# Peggy_Receiver.net
KiCad netlist of a schematic drawn in Altium Designer
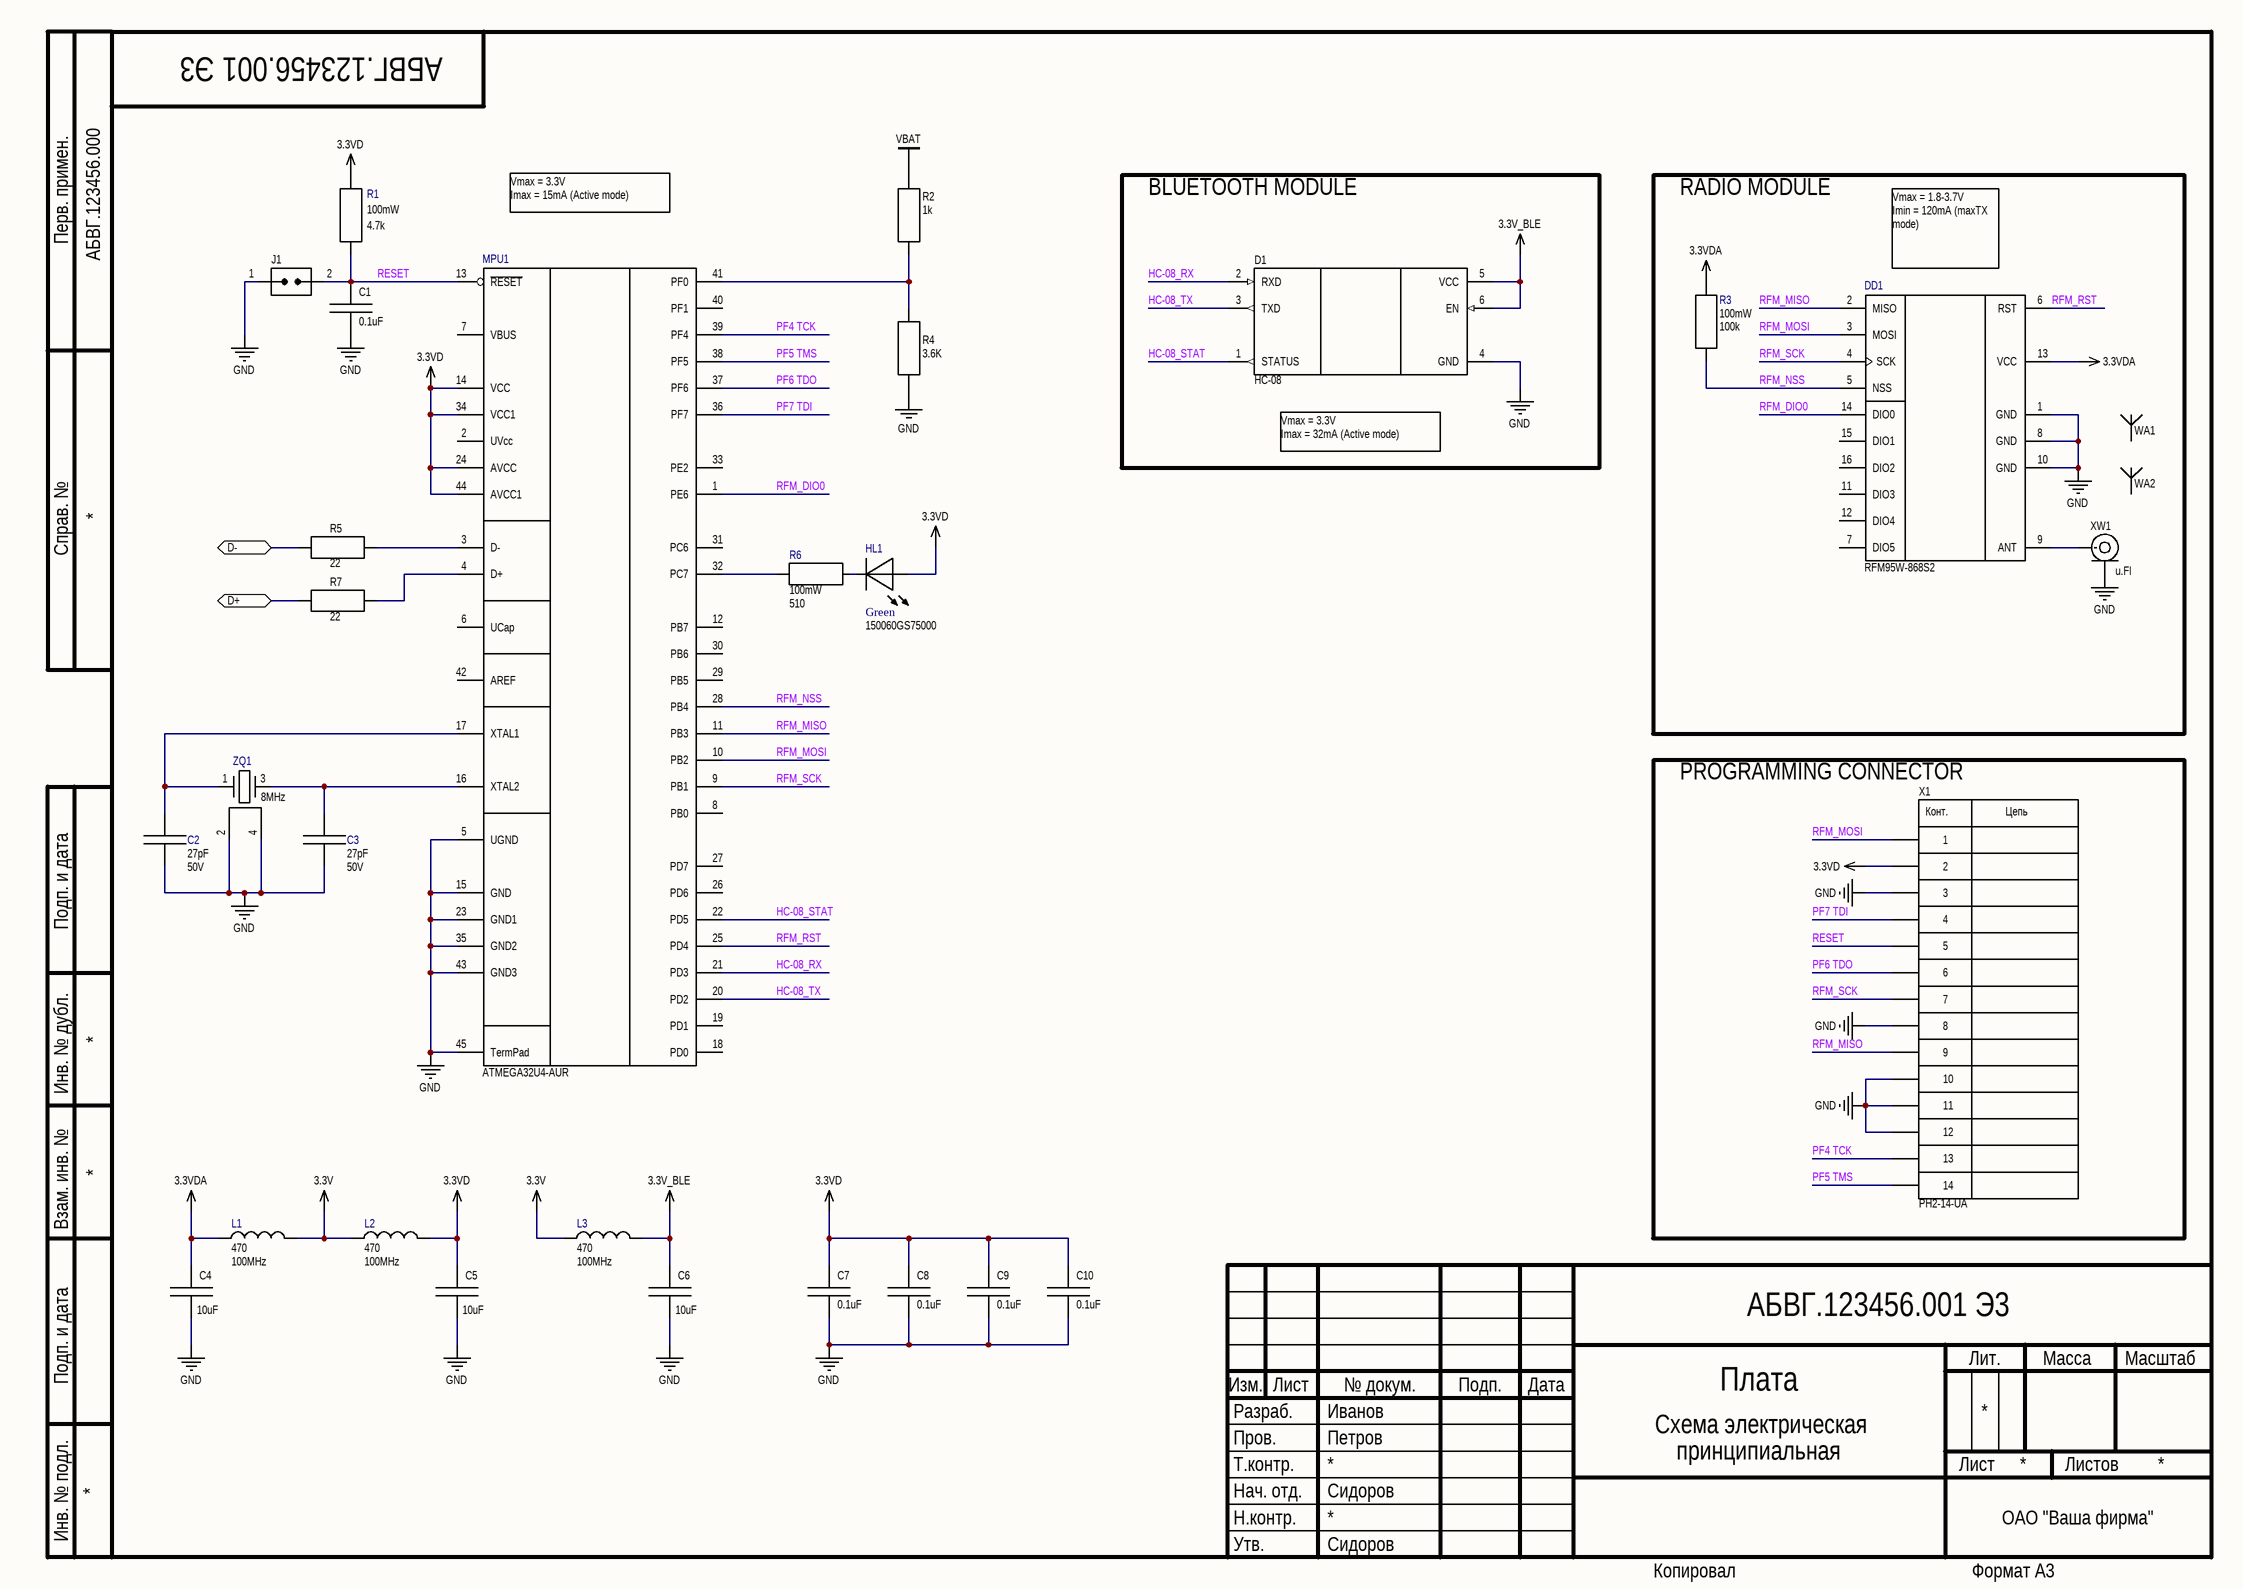
[diagram p0: Блок МК и радиомодуля Peggy Receiver.SchDoc]

(export (version "E")
  (design (tool "Eeschema 10.0.6"))
  (components
    (comp (ref "C1")
      (value "0.1uF")
      (footprint "CH0603C")
      (fields (field (name "MANUFACTURER") "Murata Electronics"))
      (libsource (lib "Discrete") (part "Capacitor"))
    )
    (comp (ref "C2")
      (value "CC0603JPNPO9BN270")
      (footprint "CAPC1608X87X35NL15T15")
      (description "0603 50V C0G 27pF 5% multilayer ceramic capacitor")
      (fields
        (field (name "MANUFACTURER") "YAGEO")
        (field (name "CAPACITANCE") "27pF")
        (field (name "VOLTAGE RATING") "50V")
        (field (name "TOLERANCE") "5%")
      )
      (libsource (lib "Sergek Concord Server") (part "CAP-NP-2"))
    )
    (comp (ref "C3")
      (value "CC0603JPNPO9BN270")
      (footprint "CAPC1608X87X35NL15T15")
      (description "0603 50V C0G 27pF 5% multilayer ceramic capacitor")
      (fields
        (field (name "MANUFACTURER") "YAGEO")
        (field (name "CAPACITANCE") "27pF")
        (field (name "VOLTAGE RATING") "50V")
        (field (name "TOLERANCE") "5%")
      )
      (libsource (lib "Sergek Concord Server") (part "CAP-NP-2"))
    )
    (comp (ref "C4")
      (value "10uF")
      (footprint "standard_dis:CH1206C")
      (description "CAP CER 10UF 16V X7R 1206")
      (fields (field (name "MANUFACTURER") "Murata Electronics"))
      (libsource (lib "Discrete") (part "Capacitor"))
    )
    (comp (ref "C5")
      (value "10uF")
      (footprint "standard_dis:CH1206C")
      (description "CAP CER 10UF 16V X7R 1206")
      (fields (field (name "MANUFACTURER") "Murata Electronics"))
      (libsource (lib "Discrete") (part "Capacitor"))
    )
    (comp (ref "C6")
      (value "10uF")
      (footprint "standard_dis:CH1206C")
      (description "CAP CER 10UF 16V X7R 1206")
      (fields (field (name "MANUFACTURER") "Murata Electronics"))
      (libsource (lib "Discrete") (part "Capacitor"))
    )
    (comp (ref "C7")
      (value "0.1uF")
      (footprint "CH0603C")
      (fields (field (name "MANUFACTURER") "Murata Electronics"))
      (libsource (lib "Discrete") (part "Capacitor"))
    )
    (comp (ref "C8")
      (value "0.1uF")
      (footprint "CH0603C")
      (fields (field (name "MANUFACTURER") "Murata Electronics"))
      (libsource (lib "Discrete") (part "Capacitor"))
    )
    (comp (ref "C9")
      (value "0.1uF")
      (footprint "CH0603C")
      (fields (field (name "MANUFACTURER") "Murata Electronics"))
      (libsource (lib "Discrete") (part "Capacitor"))
    )
    (comp (ref "C10")
      (value "0.1uF")
      (footprint "CH0603C")
      (fields (field (name "MANUFACTURER") "Murata Electronics"))
      (libsource (lib "Discrete") (part "Capacitor"))
    )
    (comp (ref "D1")
      (value "HC-08")
      (footprint "custom_mod:MOD: SH-HC-08")
      (description "Bluetooth 4.0 module")
      (fields (field (name "MANUFACTURER") "China"))
      (libsource (lib "Module") (part "HC-08"))
    )
    (comp (ref "DD1")
      (value "RFM95W-868S2")
      (footprint "RFM95W-868S2")
      (description "RF TXRX MODULE ISM<1GHZ")
      (fields
        (field (name "MANUFACTURER") "RF Solutions")
        (field (name "MANUFACTURER PART NUMBER") "RFM95W-868S2")
      )
      (libsource (lib "Sergek Concord Server") (part "HPD13A (RFM95)"))
    )
    (comp (ref "HL1")
      (value "150060GS75000")
      (footprint "CH0603LG")
      (description "WURTH ELEKTRONIK - 150060GS75000 - LED, Green, 520 nm, 3.2 V, 30 mA, 430 mcd RoHS Compliant: Yes")
      (fields
        (field (name "COLOR") "Green")
        (field (name "MANUFACTURER PART NUMBER") "150060GS75000")
        (field (name "MANUFACTURER") "Würth Elektronik")
      )
      (libsource (lib "Sergek Concord Server") (part "Symbol"))
    )
    (comp (ref "J1")
      (value "Jumper-2")
      (footprint "custom_con:CON: JUMPER_2")
      (description "Jumper")
      (fields (field (name "MANUFACTURER") "China"))
      (libsource (lib "Connectors") (part "Jumper-2"))
    )
    (comp (ref "L1")
      (value "MH2029-471Y")
      (footprint "MH2029-471Y-Footprint-1")
      (description "Ferrite Beads High Current Chip 470Ohm 25% 100MHz 1A 0.2Ohm DCR 0805 T/R")
      (fields
        (field (name "TOLERANCE") "25%")
        (field (name "IMPEDANCE") "470")
        (field (name "TEST FREQUENCY") "100MHz")
        (field (name "MANUFACTURER") "Bourns Inc.")
      )
      (libsource (lib "Sergek Concord Server") (part "IND-2"))
    )
    (comp (ref "L2")
      (value "MH2029-471Y")
      (footprint "MH2029-471Y-Footprint-1")
      (description "Ferrite Beads High Current Chip 470Ohm 25% 100MHz 1A 0.2Ohm DCR 0805 T/R")
      (fields
        (field (name "TOLERANCE") "25%")
        (field (name "IMPEDANCE") "470")
        (field (name "TEST FREQUENCY") "100MHz")
        (field (name "MANUFACTURER") "Bourns Inc.")
      )
      (libsource (lib "Sergek Concord Server") (part "IND-2"))
    )
    (comp (ref "L3")
      (value "MH2029-471Y")
      (footprint "MH2029-471Y-Footprint-1")
      (description "Ferrite Beads High Current Chip 470Ohm 25% 100MHz 1A 0.2Ohm DCR 0805 T/R")
      (fields
        (field (name "TOLERANCE") "25%")
        (field (name "IMPEDANCE") "470")
        (field (name "TEST FREQUENCY") "100MHz")
        (field (name "MANUFACTURER") "Bourns Inc.")
      )
      (libsource (lib "Sergek Concord Server") (part "IND-2"))
    )
    (comp (ref "MPU1")
      (value "ATMEGA32U4-AU")
      (footprint "ATMEGA32U4-MU")
      (fields
        (field (name "MANUFACTURER PART NUMBER") "ATMEGA32U4-AUR")
        (field (name "MANUFACTURER") "Atmel")
      )
      (libsource (lib "Sergek Concord Server") (part "ATMEGA32U4-AU"))
    )
    (comp (ref "R1")
      (value "RMCF0603FT4K70")
      (footprint "CH0603R")
      (description "Res Thick Film 0603 4.7K Ohm 1% 1/10W 100ppm/C Molded SMD SMD Paper T/R")
      (fields
        (field (name "TOLERANCE") "1%")
        (field (name "POWER RATING") "100mW")
        (field (name "RESISTANCE") "4.7k")
        (field (name "MANUFACTURER") "Stackpole Electronics Inc")
      )
      (libsource (lib "Sergek Concord Server") (part "RES-2"))
    )
    (comp (ref "R2")
      (value "1k")
      (footprint "standard_dis:CH0603R")
      (fields (field (name "MANUFACTURER") "YAGEO"))
      (libsource (lib "Discrete") (part "Resistor"))
    )
    (comp (ref "R3")
      (value "100k")
      (footprint "RESC1608X55X25NL10T15")
      (description "Chip Resistor, 100 KOhm, +/- 1%, 0.1 W, -55 to 155 degC, 0603 (1608 Metric)")
      (fields
        (field (name "POWER") "100mW")
        (field (name "TOLERANCE") "1%")
        (field (name "Comment") "Resistor 100k +/-1% 0603 100 mW")
      )
      (libsource (lib "Sergek Concord Server") (part "RES-2"))
    )
    (comp (ref "R4")
      (value "3.6K")
      (footprint "standard_dis:CH0603R")
      (description "RES 3.6K OHM 1% 1/10W 0603")
      (fields (field (name "MANUFACTURER") "YAGEO"))
      (libsource (lib "Discrete") (part "Resistor"))
    )
    (comp (ref "R5")
      (value "22")
      (footprint "standard_dis:CH0603R")
      (description "RES 22 OHM 1% 1/10W 0603")
      (fields (field (name "MANUFACTURER") "YAGEO"))
      (libsource (lib "") (part "Resistor_1"))
    )
    (comp (ref "R6")
      (value "RMCF0603JT510R")
      (footprint "RESC1608X55X25NL10T15")
      (description "510 Ohms ±5% 0.1W, 1/10W Chip Resistor 0603 (1608 Metric) Automotive AEC-Q200 Thick Film")
      (fields
        (field (name "MANUFACTURER") "Stackpole Electronics Inc")
        (field (name "POWER RATING") "100mW")
        (field (name "RESISTANCE") "510")
        (field (name "TOLERANCE") "5%")
      )
      (libsource (lib "") (part "RES-2_1"))
    )
    (comp (ref "R7")
      (value "22")
      (footprint "standard_dis:CH0603R")
      (description "RES 22 OHM 1% 1/10W 0603")
      (fields (field (name "MANUFACTURER") "YAGEO"))
      (libsource (lib "") (part "Resistor_1"))
    )
    (comp (ref "WA1")
      (value "AEACAQ190012-S915")
      (description "1.583GHz GPS Ceramic Patch RF Antenna 1.559GHz ~ 1.610GHz 17dBi - -")
      (fields (field (name "MANUFACTURER") "Abracon LLC"))
      (libsource (lib "Analog") (part "Antenna 1pin"))
    )
    (comp (ref "WA2")
      (value "2111400100")
      (description "1.583GHz GPS Ceramic Patch RF Antenna 1.559GHz ~ 1.610GHz 17dBi - -")
      (fields (field (name "MANUFACTURER") "Molex"))
      (libsource (lib "Analog") (part "Antenna 1pin"))
    )
    (comp (ref "X1")
      (value "PH2-14-UA")
      (footprint "custom_con:CON: PLD-14_SHIFTED")
      (fields (field (name "MANUFACTURER") "Adam Tech"))
      (libsource (lib "Connectors") (part "14-Connector"))
    )
    (comp (ref "XW1")
      (value "u.Fl")
      (footprint "custom_con:CON: u.Fl")
      (description "RF")
      (fields (field (name "MANUFACTURER") "Hirose Electric Co Ltd"))
      (libsource (lib "Connectors") (part "u.Fl"))
    )
    (comp (ref "ZQ1")
      (value "FY0800018")
      (footprint "FY0800018-Footprint-1")
      (description "Crystal 8MHz ±30ppm (Tol) ±30ppm (Stability) 18pF FUND 100Ohm 4-Pin SMD T/R")
      (fields (field (name "MANUFACTURER") "Diodes Incorporated") (field (name "FREQUENCY") "8MHz"))
      (libsource (lib "Sergek Concord Server") (part "XTAL-2"))
    )
  )
  (nets
    (net (code "1") (name "/D+") (class "Default")
      (node (ref "R7") (pin "1") (pinfunction "1_1") (pintype "passive"))
    )
    (net (code "2") (name "/D-") (class "Default")
      (node (ref "R5") (pin "1") (pinfunction "1_1") (pintype "passive"))
    )
    (net (code "3") (name "/HC-08_RX") (class "Default")
      (node (ref "D1") (pin "2") (pinfunction "RXD_2") (pintype "input"))
      (node (ref "MPU1") (pin "21") (pinfunction "PD3_21") (pintype "passive"))
    )
    (net (code "4") (name "/HC-08_STAT") (class "Default")
      (node (ref "D1") (pin "1") (pinfunction "STATUS_1") (pintype "output"))
      (node (ref "MPU1") (pin "22") (pinfunction "PD5_22") (pintype "passive"))
    )
    (net (code "5") (name "/HC-08_TX") (class "Default")
      (node (ref "D1") (pin "3") (pinfunction "TXD_3") (pintype "output"))
      (node (ref "MPU1") (pin "20") (pinfunction "PD2_20") (pintype "passive"))
    )
    (net (code "6") (name "/PF4 TCK") (class "Default")
      (node (ref "MPU1") (pin "39") (pinfunction "PF4_39") (pintype "passive"))
      (node (ref "X1") (pin "13") (pinfunction "13_13") (pintype "power_in"))
    )
    (net (code "7") (name "/PF5 TMS") (class "Default")
      (node (ref "MPU1") (pin "38") (pinfunction "PF5_38") (pintype "passive"))
      (node (ref "X1") (pin "14") (pinfunction "14_14") (pintype "power_in"))
    )
    (net (code "8") (name "/PF6 TDO") (class "Default")
      (node (ref "MPU1") (pin "37") (pinfunction "PF6_37") (pintype "passive"))
      (node (ref "X1") (pin "6") (pinfunction "6_6") (pintype "passive"))
    )
    (net (code "9") (name "/PF7 TDI") (class "Default")
      (node (ref "MPU1") (pin "36") (pinfunction "PF7_36") (pintype "passive"))
      (node (ref "X1") (pin "4") (pinfunction "4_4") (pintype "power_in"))
    )
    (net (code "10") (name "/RESET") (class "Default")
      (node (ref "C1") (pin "1") (pinfunction "1_1") (pintype "passive"))
      (node (ref "J1") (pin "2") (pinfunction "IN_2") (pintype "passive"))
      (node (ref "MPU1") (pin "13") (pinfunction "~{RESET}_13") (pintype "passive"))
      (node (ref "R1") (pin "1") (pinfunction "1_1") (pintype "passive"))
      (node (ref "X1") (pin "5") (pinfunction "5_5") (pintype "power_in"))
    )
    (net (code "11") (name "/RFM_DIO0") (class "Default")
      (node (ref "DD1") (pin "14") (pinfunction "DIO0_14") (pintype "passive"))
      (node (ref "MPU1") (pin "1") (pinfunction "PE6_1") (pintype "passive"))
    )
    (net (code "12") (name "/RFM_MISO") (class "Default")
      (node (ref "DD1") (pin "2") (pinfunction "MISO_2") (pintype "passive"))
      (node (ref "MPU1") (pin "11") (pinfunction "PB3_11") (pintype "passive"))
      (node (ref "X1") (pin "9") (pinfunction "9_9") (pintype "power_in"))
    )
    (net (code "13") (name "/RFM_MOSI") (class "Default")
      (node (ref "DD1") (pin "3") (pinfunction "MOSI_3") (pintype "passive"))
      (node (ref "MPU1") (pin "10") (pinfunction "PB2_10") (pintype "passive"))
      (node (ref "X1") (pin "1") (pinfunction "1_1") (pintype "passive"))
    )
    (net (code "14") (name "/RFM_NSS") (class "Default")
      (node (ref "DD1") (pin "5") (pinfunction "NSS_5") (pintype "passive"))
      (node (ref "MPU1") (pin "28") (pinfunction "PB4_28") (pintype "passive"))
      (node (ref "R3") (pin "1") (pinfunction "1_1") (pintype "passive"))
    )
    (net (code "15") (name "/RFM_RST") (class "Default")
      (node (ref "DD1") (pin "6") (pinfunction "RST_6") (pintype "passive"))
      (node (ref "MPU1") (pin "25") (pinfunction "PD4_25") (pintype "passive"))
    )
    (net (code "16") (name "/RFM_SCK") (class "Default")
      (node (ref "DD1") (pin "4") (pinfunction "SCK_4") (pintype "passive"))
      (node (ref "MPU1") (pin "9") (pinfunction "PB1_9") (pintype "passive"))
      (node (ref "X1") (pin "7") (pinfunction "7_7") (pintype "passive"))
    )
    (net (code "17") (name "3.3V") (class "Default")
      (node (ref "L1") (pin "2") (pinfunction "2_2") (pintype "passive"))
      (node (ref "L2") (pin "1") (pinfunction "1_1") (pintype "passive"))
      (node (ref "L3") (pin "1") (pinfunction "1_1") (pintype "passive"))
    )
    (net (code "18") (name "3.3VD") (class "Default")
      (node (ref "C10") (pin "1") (pinfunction "1_1") (pintype "passive"))
      (node (ref "C5") (pin "1") (pinfunction "1_1") (pintype "passive"))
      (node (ref "C7") (pin "1") (pinfunction "1_1") (pintype "passive"))
      (node (ref "C8") (pin "1") (pinfunction "1_1") (pintype "passive"))
      (node (ref "C9") (pin "1") (pinfunction "1_1") (pintype "passive"))
      (node (ref "HL1") (pin "2") (pinfunction "2_2") (pintype "passive"))
      (node (ref "L2") (pin "2") (pinfunction "2_2") (pintype "passive"))
      (node (ref "MPU1") (pin "14") (pinfunction "VCC_14") (pintype "passive"))
      (node (ref "MPU1") (pin "24") (pinfunction "AVCC_24") (pintype "passive"))
      (node (ref "MPU1") (pin "34") (pinfunction "VCC1_34") (pintype "passive"))
      (node (ref "MPU1") (pin "44") (pinfunction "AVCC1_44") (pintype "passive"))
      (node (ref "R1") (pin "2") (pinfunction "2_2") (pintype "passive"))
      (node (ref "X1") (pin "2") (pinfunction "2_2") (pintype "passive"))
    )
    (net (code "19") (name "3.3VDA") (class "Default")
      (node (ref "C4") (pin "1") (pinfunction "1_1") (pintype "passive"))
      (node (ref "DD1") (pin "13") (pinfunction "VCC_13") (pintype "passive"))
      (node (ref "L1") (pin "1") (pinfunction "1_1") (pintype "passive"))
      (node (ref "R3") (pin "2") (pinfunction "2_2") (pintype "passive"))
    )
    (net (code "20") (name "3.3V_BLE") (class "Default")
      (node (ref "C6") (pin "1") (pinfunction "1_1") (pintype "passive"))
      (node (ref "D1") (pin "5") (pinfunction "VCC_5") (pintype "power_in"))
      (node (ref "D1") (pin "6") (pinfunction "EN_6") (pintype "input"))
      (node (ref "L3") (pin "2") (pinfunction "2_2") (pintype "passive"))
    )
    (net (code "21") (name "GND") (class "Default")
      (node (ref "C1") (pin "2") (pinfunction "2_2") (pintype "passive"))
      (node (ref "C10") (pin "2") (pinfunction "2_2") (pintype "passive"))
      (node (ref "C2") (pin "1") (pinfunction "1_1") (pintype "passive"))
      (node (ref "C3") (pin "1") (pinfunction "1_1") (pintype "passive"))
      (node (ref "C4") (pin "2") (pinfunction "2_2") (pintype "passive"))
      (node (ref "C5") (pin "2") (pinfunction "2_2") (pintype "passive"))
      (node (ref "C6") (pin "2") (pinfunction "2_2") (pintype "passive"))
      (node (ref "C7") (pin "2") (pinfunction "2_2") (pintype "passive"))
      (node (ref "C8") (pin "2") (pinfunction "2_2") (pintype "passive"))
      (node (ref "C9") (pin "2") (pinfunction "2_2") (pintype "passive"))
      (node (ref "D1") (pin "4") (pinfunction "GND_4") (pintype "power_in"))
      (node (ref "DD1") (pin "1") (pinfunction "GND_1") (pintype "passive"))
      (node (ref "DD1") (pin "10") (pinfunction "GND_10") (pintype "passive"))
      (node (ref "DD1") (pin "8") (pinfunction "GND_8") (pintype "passive"))
      (node (ref "J1") (pin "1") (pinfunction "IN_1") (pintype "passive"))
      (node (ref "MPU1") (pin "15") (pinfunction "GND_15") (pintype "passive"))
      (node (ref "MPU1") (pin "23") (pinfunction "GND1_23") (pintype "passive"))
      (node (ref "MPU1") (pin "35") (pinfunction "GND2_35") (pintype "passive"))
      (node (ref "MPU1") (pin "43") (pinfunction "GND3_43") (pintype "passive"))
      (node (ref "MPU1") (pin "45") (pinfunction "TermPad_45") (pintype "passive"))
      (node (ref "MPU1") (pin "5") (pinfunction "UGND_5") (pintype "passive"))
      (node (ref "R4") (pin "1") (pinfunction "1_1") (pintype "passive"))
      (node (ref "X1") (pin "10") (pinfunction "10_10") (pintype "power_in"))
      (node (ref "X1") (pin "11") (pinfunction "11_11") (pintype "power_in"))
      (node (ref "X1") (pin "12") (pinfunction "12_12") (pintype "power_in"))
      (node (ref "X1") (pin "3") (pinfunction "3_3") (pintype "power_in"))
      (node (ref "X1") (pin "8") (pinfunction "8_8") (pintype "power_in"))
      (node (ref "XW1") (pin "2") (pinfunction "IN_2") (pintype "passive"))
      (node (ref "ZQ1") (pin "2") (pinfunction "2_2") (pintype "passive"))
      (node (ref "ZQ1") (pin "4") (pinfunction "4_4") (pintype "passive"))
    )
    (net (code "22") (name "Net-(DD1-ANT)") (class "Default")
      (node (ref "DD1") (pin "9") (pinfunction "ANT_9") (pintype "passive"))
      (node (ref "XW1") (pin "1") (pinfunction "IN_1") (pintype "passive"))
    )
    (net (code "23") (name "Net-(HL1-Pad1)") (class "Default")
      (node (ref "HL1") (pin "1") (pinfunction "1_1") (pintype "passive"))
      (node (ref "R6") (pin "2") (pinfunction "2_2") (pintype "passive"))
    )
    (net (code "24") (name "Net-(MPU1-D+)") (class "Default")
      (node (ref "MPU1") (pin "4") (pinfunction "D+_4") (pintype "passive"))
      (node (ref "R7") (pin "2") (pinfunction "2_2") (pintype "passive"))
    )
    (net (code "25") (name "Net-(MPU1-D-)") (class "Default")
      (node (ref "MPU1") (pin "3") (pinfunction "D-_3") (pintype "passive"))
      (node (ref "R5") (pin "2") (pinfunction "2_2") (pintype "passive"))
    )
    (net (code "26") (name "Net-(MPU1-PC7)") (class "Default")
      (node (ref "MPU1") (pin "32") (pinfunction "PC7_32") (pintype "passive"))
      (node (ref "R6") (pin "1") (pinfunction "1_1") (pintype "passive"))
    )
    (net (code "27") (name "Net-(MPU1-PF0)") (class "Default")
      (node (ref "MPU1") (pin "41") (pinfunction "PF0_41") (pintype "passive"))
      (node (ref "R2") (pin "1") (pinfunction "1_1") (pintype "passive"))
      (node (ref "R4") (pin "2") (pinfunction "2_2") (pintype "passive"))
    )
    (net (code "28") (name "Net-(MPU1-XTAL1)") (class "Default")
      (node (ref "C2") (pin "2") (pinfunction "2_2") (pintype "passive"))
      (node (ref "MPU1") (pin "17") (pinfunction "XTAL1_17") (pintype "passive"))
      (node (ref "ZQ1") (pin "1") (pinfunction "1_1") (pintype "passive"))
    )
    (net (code "29") (name "Net-(MPU1-XTAL2)") (class "Default")
      (node (ref "C3") (pin "2") (pinfunction "2_2") (pintype "passive"))
      (node (ref "MPU1") (pin "16") (pinfunction "XTAL2_16") (pintype "passive"))
      (node (ref "ZQ1") (pin "3") (pinfunction "3_3") (pintype "passive"))
    )
    (net (code "30") (name "VBAT") (class "Default")
      (node (ref "R2") (pin "2") (pinfunction "2_2") (pintype "passive"))
    )
    (net (code "31") (name "unconnected-(DD1-DIO1-Pad15)") (class "Default")
      (node (ref "DD1") (pin "15") (pinfunction "DIO1_15") (pintype "passive"))
    )
    (net (code "32") (name "unconnected-(DD1-DIO2-Pad16)") (class "Default")
      (node (ref "DD1") (pin "16") (pinfunction "DIO2_16") (pintype "passive"))
    )
    (net (code "33") (name "unconnected-(DD1-DIO3-Pad11)") (class "Default")
      (node (ref "DD1") (pin "11") (pinfunction "DIO3_11") (pintype "passive"))
    )
    (net (code "34") (name "unconnected-(DD1-DIO4-Pad12)") (class "Default")
      (node (ref "DD1") (pin "12") (pinfunction "DIO4_12") (pintype "passive"))
    )
    (net (code "35") (name "unconnected-(DD1-DIO5-Pad7)") (class "Default")
      (node (ref "DD1") (pin "7") (pinfunction "DIO5_7") (pintype "passive"))
    )
    (net (code "36") (name "unconnected-(MPU1-AREF-Pad42)") (class "Default")
      (node (ref "MPU1") (pin "42") (pinfunction "AREF_42") (pintype "passive"))
    )
    (net (code "37") (name "unconnected-(MPU1-PB0-Pad8)") (class "Default")
      (node (ref "MPU1") (pin "8") (pinfunction "PB0_8") (pintype "passive"))
    )
    (net (code "38") (name "unconnected-(MPU1-PB5-Pad29)") (class "Default")
      (node (ref "MPU1") (pin "29") (pinfunction "PB5_29") (pintype "passive"))
    )
    (net (code "39") (name "unconnected-(MPU1-PB6-Pad30)") (class "Default")
      (node (ref "MPU1") (pin "30") (pinfunction "PB6_30") (pintype "passive"))
    )
    (net (code "40") (name "unconnected-(MPU1-PB7-Pad12)") (class "Default")
      (node (ref "MPU1") (pin "12") (pinfunction "PB7_12") (pintype "passive"))
    )
    (net (code "41") (name "unconnected-(MPU1-PC6-Pad31)") (class "Default")
      (node (ref "MPU1") (pin "31") (pinfunction "PC6_31") (pintype "passive"))
    )
    (net (code "42") (name "unconnected-(MPU1-PD0-Pad18)") (class "Default")
      (node (ref "MPU1") (pin "18") (pinfunction "PD0_18") (pintype "passive"))
    )
    (net (code "43") (name "unconnected-(MPU1-PD1-Pad19)") (class "Default")
      (node (ref "MPU1") (pin "19") (pinfunction "PD1_19") (pintype "passive"))
    )
    (net (code "44") (name "unconnected-(MPU1-PD6-Pad26)") (class "Default")
      (node (ref "MPU1") (pin "26") (pinfunction "PD6_26") (pintype "passive"))
    )
    (net (code "45") (name "unconnected-(MPU1-PD7-Pad27)") (class "Default")
      (node (ref "MPU1") (pin "27") (pinfunction "PD7_27") (pintype "passive"))
    )
    (net (code "46") (name "unconnected-(MPU1-PE2-Pad33)") (class "Default")
      (node (ref "MPU1") (pin "33") (pinfunction "PE2_33") (pintype "passive"))
    )
    (net (code "47") (name "unconnected-(MPU1-PF1-Pad40)") (class "Default")
      (node (ref "MPU1") (pin "40") (pinfunction "PF1_40") (pintype "passive"))
    )
    (net (code "48") (name "unconnected-(MPU1-UCap-Pad6)") (class "Default")
      (node (ref "MPU1") (pin "6") (pinfunction "UCap_6") (pintype "passive"))
    )
    (net (code "49") (name "unconnected-(MPU1-UVcc-Pad2)") (class "Default")
      (node (ref "MPU1") (pin "2") (pinfunction "UVcc_2") (pintype "passive"))
    )
    (net (code "50") (name "unconnected-(MPU1-VBUS-Pad7)") (class "Default")
      (node (ref "MPU1") (pin "7") (pinfunction "VBUS_7") (pintype "passive"))
    )
    (net (code "51") (name "unconnected-(WA1-Pad1)") (class "Default")
      (node (ref "WA1") (pin "1") (pinfunction "1_1") (pintype "passive"))
    )
    (net (code "52") (name "unconnected-(WA2-Pad1)") (class "Default")
      (node (ref "WA2") (pin "1") (pinfunction "1_1") (pintype "passive"))
    )
  )
)
